# Schematic1_projectTSC_v31.net
KiCad netlist of a schematic drawn in EAGLE
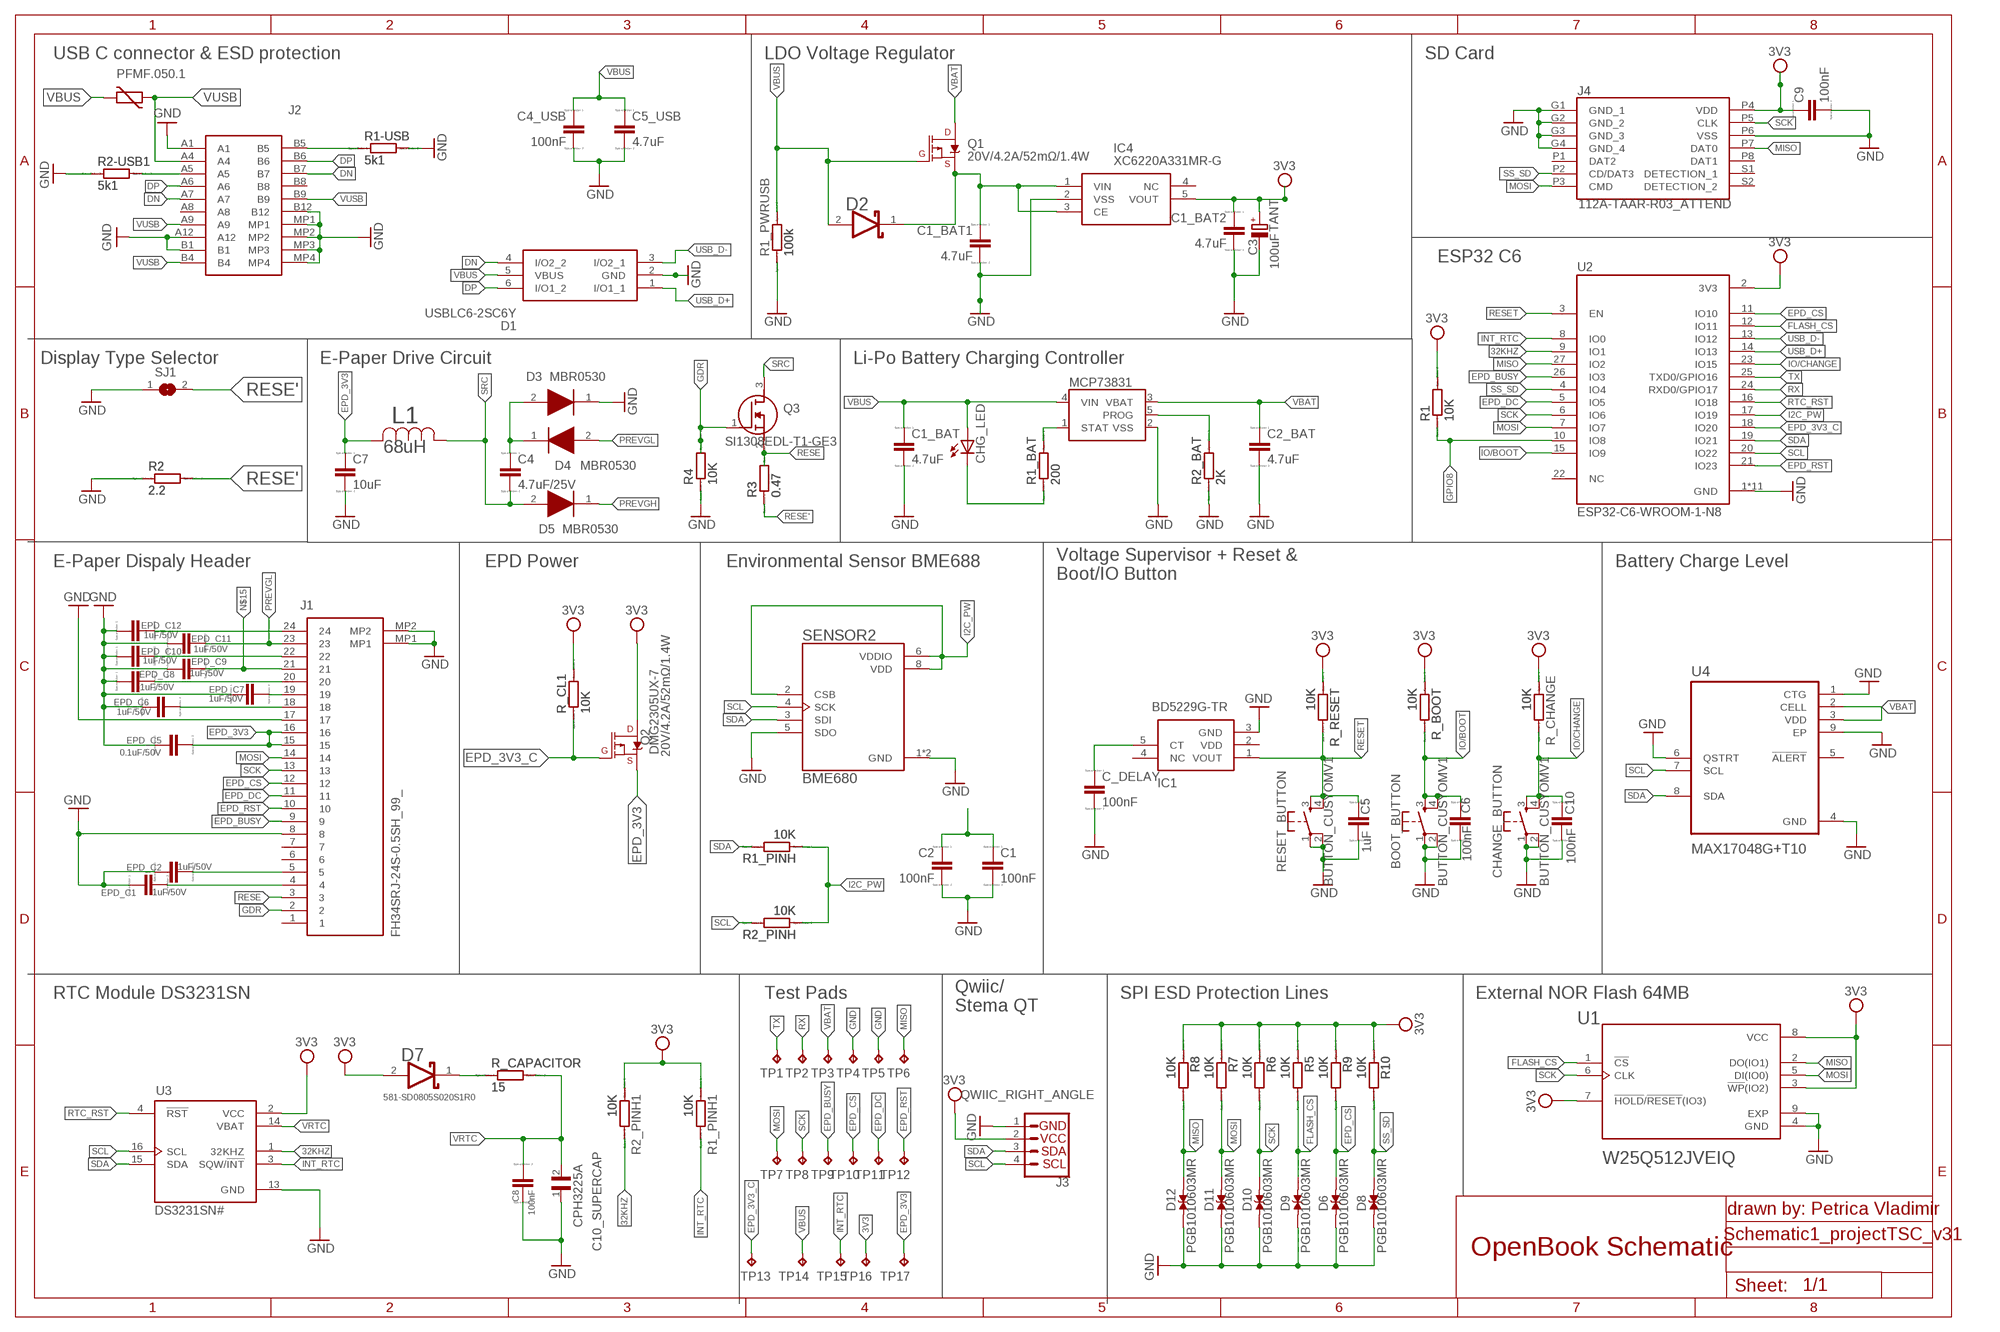
[diagram p0: schematic, sheet 1]

(export (version "E")
  (design (tool "Eeschema 10.0.6"))
  (components
    (comp (ref "BOOT_BUTTON")
      (value "BUTTON_CUSYOMV1")
      (footprint "eagle-import:MYBUTTON")
      (libsource (lib "eagle-import") (part "BUTTON_CUSYOMV1"))
    )
    (comp (ref "C1")
      (value "100nF")
      (footprint "eagle-import:EAGLE-LTSPICE_C0402")
      (libsource (lib "eagle-import") (part "EAGLE-LTSPICE_CC0402"))
    )
    (comp (ref "C1_BAT")
      (value "4.7uF")
      (footprint "eagle-import:EAGLE-LTSPICE_C0402")
      (libsource (lib "eagle-import") (part "EAGLE-LTSPICE_CC0402"))
    )
    (comp (ref "C1_BAT1")
      (value "4.7uF")
      (footprint "eagle-import:EAGLE-LTSPICE_C0402")
      (libsource (lib "eagle-import") (part "EAGLE-LTSPICE_CC0402"))
    )
    (comp (ref "C1_BAT2")
      (value "4.7uF")
      (footprint "eagle-import:EAGLE-LTSPICE_C0402")
      (libsource (lib "eagle-import") (part "EAGLE-LTSPICE_CC0402"))
    )
    (comp (ref "C2")
      (value "100nF")
      (footprint "eagle-import:EAGLE-LTSPICE_C0402")
      (libsource (lib "eagle-import") (part "EAGLE-LTSPICE_CC0402"))
    )
    (comp (ref "C2_BAT")
      (value "4.7uF")
      (footprint "eagle-import:EAGLE-LTSPICE_C0402")
      (libsource (lib "eagle-import") (part "EAGLE-LTSPICE_CC0402"))
    )
    (comp (ref "C3")
      (value "100uF")
      (footprint "eagle-import:RCL_CT3528")
      (libsource (lib "eagle-import") (part "RCL_CPOL-EUCT3528"))
    )
    (comp (ref "C4")
      (value "4.7uF/25V")
      (footprint "eagle-import:EAGLE-LTSPICE_C0402")
      (libsource (lib "eagle-import") (part "EAGLE-LTSPICE_CC0402"))
    )
    (comp (ref "C4_USB")
      (value "100nF")
      (footprint "eagle-import:EAGLE-LTSPICE_C0402")
      (libsource (lib "eagle-import") (part "EAGLE-LTSPICE_CC0402"))
    )
    (comp (ref "C5")
      (value "1uF")
      (footprint "eagle-import:EAGLE-LTSPICE_C0402")
      (libsource (lib "eagle-import") (part "EAGLE-LTSPICE_CC0402"))
    )
    (comp (ref "C5_USB")
      (value "4.7uF")
      (footprint "eagle-import:EAGLE-LTSPICE_C0402")
      (libsource (lib "eagle-import") (part "EAGLE-LTSPICE_CC0402"))
    )
    (comp (ref "C6")
      (value "100nF")
      (footprint "eagle-import:EAGLE-LTSPICE_C0402")
      (libsource (lib "eagle-import") (part "EAGLE-LTSPICE_CC0402"))
    )
    (comp (ref "C7")
      (value "10uF")
      (footprint "eagle-import:EAGLE-LTSPICE_C0402")
      (libsource (lib "eagle-import") (part "EAGLE-LTSPICE_CC0402"))
    )
    (comp (ref "C8")
      (value "100nF")
      (footprint "eagle-import:EAGLE-LTSPICE_C0402")
      (libsource (lib "eagle-import") (part "EAGLE-LTSPICE_CC0402"))
    )
    (comp (ref "C9")
      (value "100nF")
      (footprint "eagle-import:EAGLE-LTSPICE_C0402")
      (libsource (lib "eagle-import") (part "EAGLE-LTSPICE_CC0402"))
    )
    (comp (ref "C10")
      (value "100nF")
      (footprint "eagle-import:EAGLE-LTSPICE_C0402")
      (libsource (lib "eagle-import") (part "EAGLE-LTSPICE_CC0402"))
    )
    (comp (ref "C10_SUPERCAP")
      (value "CPH3225A")
      (footprint "eagle-import:CAPCP3225X100N")
      (fields (field (name "MF") "Seiko Instruments"))
      (libsource (lib "eagle-import") (part "CPH3225A"))
    )
    (comp (ref "CHANGE_BUTTON")
      (value "BUTTON_CUSYOMV1")
      (footprint "eagle-import:MYBUTTON")
      (libsource (lib "eagle-import") (part "BUTTON_CUSYOMV1"))
    )
    (comp (ref "CHG_LED")
      (value "ADAFRUIT_LEDCHIP-LED0603")
      (footprint "eagle-import:ADAFRUIT_CHIP-LED0603")
      (libsource (lib "eagle-import") (part "ADAFRUIT_LEDCHIP-LED0603"))
    )
    (comp (ref "C_DELAY")
      (value "100nF")
      (footprint "eagle-import:EAGLE-LTSPICE_C0402")
      (libsource (lib "eagle-import") (part "EAGLE-LTSPICE_CC0402"))
    )
    (comp (ref "D1")
      (value "USBLC6-2SC6Y")
      (footprint "eagle-import:SOT95P280X145-6N")
      (fields (field (name "MF") "STMicroelectronics"))
      (libsource (lib "eagle-import") (part "USBLC6-2SC6Y"))
    )
    (comp (ref "D2")
      (value "ESP32_WROVER_AVX---SD0805S020S1R0_AVX_SD0805S020S1R0_0_0AVX_SD0805S020S1R0_0_0")
      (footprint "eagle-import:ESP32_WROVER_AVX---SD0805S020S1R0_AVX_SD0805S020S1R0_0")
      (fields
        (field (name "DIGIKEY_PART_NUMBER") "478-7800-1-ND")
        (field (name "MF") "AVX")
        (field (name "MOUSER_PART_NUMBER") "581-SD0805S020S1R0")
      )
      (libsource (lib "eagle-import") (part "ESP32_WROVER_AVX---SD0805S020S1R0_AVX_SD0805S020S1R0_0_0AVX_SD0805S020S1R0_0_0"))
    )
    (comp (ref "D3")
      (value "MBR0530")
      (footprint "eagle-import:SOD3716X135N")
      (fields (field (name "MF") "ON Semiconductor"))
      (libsource (lib "eagle-import") (part "MBR0530"))
    )
    (comp (ref "D4")
      (value "MBR0530")
      (footprint "eagle-import:SOD3716X135N")
      (fields (field (name "MF") "ON Semiconductor"))
      (libsource (lib "eagle-import") (part "MBR0530"))
    )
    (comp (ref "D5")
      (value "MBR0530")
      (footprint "eagle-import:SOD3716X135N")
      (fields (field (name "MF") "ON Semiconductor"))
      (libsource (lib "eagle-import") (part "MBR0530"))
    )
    (comp (ref "D6")
      (value "PGB1010603MR")
      (footprint "eagle-import:DIOC1608X36N")
      (fields (field (name "MF") "Littelfuse Inc."))
      (libsource (lib "eagle-import") (part "PGB1010603MR"))
    )
    (comp (ref "D7")
      (value "ESP32_WROVER_AVX---SD0805S020S1R0_AVX_SD0805S020S1R0_0_0AVX_SD0805S020S1R0_0_0")
      (footprint "eagle-import:ESP32_WROVER_AVX---SD0805S020S1R0_AVX_SD0805S020S1R0_0")
      (fields
        (field (name "DIGIKEY_PART_NUMBER") "478-7800-1-ND")
        (field (name "MF") "AVX")
        (field (name "MOUSER_PART_NUMBER") "581-SD0805S020S1R0")
      )
      (libsource (lib "eagle-import") (part "ESP32_WROVER_AVX---SD0805S020S1R0_AVX_SD0805S020S1R0_0_0AVX_SD0805S020S1R0_0_0"))
    )
    (comp (ref "D8")
      (value "PGB1010603MR")
      (footprint "eagle-import:DIOC1608X36N")
      (fields (field (name "MF") "Littelfuse Inc."))
      (libsource (lib "eagle-import") (part "PGB1010603MR"))
    )
    (comp (ref "D9")
      (value "PGB1010603MR")
      (footprint "eagle-import:DIOC1608X36N")
      (fields (field (name "MF") "Littelfuse Inc."))
      (libsource (lib "eagle-import") (part "PGB1010603MR"))
    )
    (comp (ref "D10")
      (value "PGB1010603MR")
      (footprint "eagle-import:DIOC1608X36N")
      (fields (field (name "MF") "Littelfuse Inc."))
      (libsource (lib "eagle-import") (part "PGB1010603MR"))
    )
    (comp (ref "D11")
      (value "PGB1010603MR")
      (footprint "eagle-import:DIOC1608X36N")
      (fields (field (name "MF") "Littelfuse Inc."))
      (libsource (lib "eagle-import") (part "PGB1010603MR"))
    )
    (comp (ref "D12")
      (value "PGB1010603MR")
      (footprint "eagle-import:DIOC1608X36N")
      (fields (field (name "MF") "Littelfuse Inc."))
      (libsource (lib "eagle-import") (part "PGB1010603MR"))
    )
    (comp (ref "EPD_C1")
      (value "1uF/50V")
      (footprint "eagle-import:EAGLE-LTSPICE_C0402")
      (libsource (lib "eagle-import") (part "EAGLE-LTSPICE_CC0402"))
    )
    (comp (ref "EPD_C2")
      (value "1uF/50V")
      (footprint "eagle-import:EAGLE-LTSPICE_C0402")
      (libsource (lib "eagle-import") (part "EAGLE-LTSPICE_CC0402"))
    )
    (comp (ref "EPD_C5")
      (value "0.1uF/50V")
      (footprint "eagle-import:EAGLE-LTSPICE_C0402")
      (libsource (lib "eagle-import") (part "EAGLE-LTSPICE_CC0402"))
    )
    (comp (ref "EPD_C6")
      (value "1uF/50V")
      (footprint "eagle-import:EAGLE-LTSPICE_C0402")
      (libsource (lib "eagle-import") (part "EAGLE-LTSPICE_CC0402"))
    )
    (comp (ref "EPD_C7")
      (value "1uF/50V")
      (footprint "eagle-import:EAGLE-LTSPICE_C0402")
      (libsource (lib "eagle-import") (part "EAGLE-LTSPICE_CC0402"))
    )
    (comp (ref "EPD_C8")
      (value "1uF/50V")
      (footprint "eagle-import:EAGLE-LTSPICE_C0402")
      (libsource (lib "eagle-import") (part "EAGLE-LTSPICE_CC0402"))
    )
    (comp (ref "EPD_C9")
      (value "1uF/50V")
      (footprint "eagle-import:EAGLE-LTSPICE_C0402")
      (libsource (lib "eagle-import") (part "EAGLE-LTSPICE_CC0402"))
    )
    (comp (ref "EPD_C10")
      (value "1uF/50V")
      (footprint "eagle-import:EAGLE-LTSPICE_C0402")
      (libsource (lib "eagle-import") (part "EAGLE-LTSPICE_CC0402"))
    )
    (comp (ref "EPD_C11")
      (value "1uF/50V")
      (footprint "eagle-import:EAGLE-LTSPICE_C0402")
      (libsource (lib "eagle-import") (part "EAGLE-LTSPICE_CC0402"))
    )
    (comp (ref "EPD_C12")
      (value "1uF/50V")
      (footprint "eagle-import:EAGLE-LTSPICE_C0402")
      (libsource (lib "eagle-import") (part "EAGLE-LTSPICE_CC0402"))
    )
    (comp (ref "IC1")
      (value "BD5229G-TR")
      (footprint "eagle-import:SOT95P280X125-5N")
      (fields (field (name "MOUSER_PART_NUMBER") "755-BD5229G-TR"))
      (libsource (lib "eagle-import") (part "BD5229G-TR"))
    )
    (comp (ref "IC4")
      (value "XC6220A331MR-G")
      (footprint "eagle-import:SOT95P280X120-5N")
      (fields (field (name "MOUSER_PART_NUMBER") "865-XC6220A331MR-G"))
      (libsource (lib "eagle-import") (part "XC6220A331MR-G"))
    )
    (comp (ref "J1")
      (value "FH34SRJ-24S-0.5SH_99_")
      (footprint "eagle-import:FH34SRJ24S05SH99")
      (fields
        (field (name "MANUFACTURER_PART_NUMBER") "FH34SRJ-24S-0.5SH(99)")
        (field (name "MOUSER_PART_NUMBER") "798-FH34SRJ24S05SH99")
      )
      (libsource (lib "eagle-import") (part "FH34SRJ-24S-0.5SH_99_"))
    )
    (comp (ref "J2")
      (value "SAMACSYS_PARTS_USB4110-GF-A")
      (footprint "eagle-import:SAMACSYS_PARTS_USB4110GFA")
      (fields
        (field (name "MANUFACTURER_PART_NUMBER") "USB4110-GF-A")
        (field (name "MOUSER_PART_NUMBER") "640-USB4110-GF-A")
      )
      (libsource (lib "eagle-import") (part "SAMACSYS_PARTS_USB4110-GF-A"))
    )
    (comp (ref "J3")
      (value "QWIIC_RIGHT_ANGLE")
      (footprint "eagle-import:JST04_1MM_RA")
      (libsource (lib "eagle-import") (part "QWIIC_CONNECTORJS-1MM"))
    )
    (comp (ref "J4")
      (value "112A-TAAR-R03_ATTEND")
      (footprint "eagle-import:112ATAARR03ATTEND")
      (fields (field (name "MANUFACTURER_PART_NUMBER") "112A-TAAR-R03 ATTEND"))
      (libsource (lib "eagle-import") (part "112A-TAAR-R03_ATTEND"))
    )
    (comp (ref "L1")
      (value "744043680IND_4828-WE-TPC_WRE")
      (footprint "eagle-import:IND_4828-WE-TPC_WRE")
      (fields
        (field (name "MANUFACTURER_PART_NUMBER") "744043680")
        (field (name "MANUFACTURER_PART_NUMBER_1") "68uH")
        (field (name "COPYRIGHT") "Copyright (C) 2024 Ultra Librarian. All rights reserved.")
      )
      (libsource (lib "eagle-import") (part "744043680IND_4828-WE-TPC_WRE"))
    )
    (comp (ref "MCP73831")
      (value "ESP32_WROVER_SPARKFUN-IC-POWER_MCP73831")
      (footprint "eagle-import:ESP32_WROVER_SPARKFUN-IC-POWER_SOT23-5")
      (libsource (lib "eagle-import") (part "ESP32_WROVER_SPARKFUN-IC-POWER_MCP73831"))
    )
    (comp (ref "PFMF.050.1")
      (value "ESP32C6_VARISTORCN1812")
      (footprint "eagle-import:ESP32C6_VARISTOR_CT_CN1812")
      (libsource (lib "eagle-import") (part "ESP32C6_VARISTORCN1812"))
    )
    (comp (ref "Q1")
      (value "20V/4.2A/52mΩ/1.4W")
      (footprint "eagle-import:ESP32_WROVER_SPARKFUN-DISCRETESEMI_SOT23-3")
      (libsource (lib "eagle-import") (part "ESP32_WROVER_SPARKFUN-DISCRETESEMI_MOSFET_PCH-DMG2305UX-7"))
    )
    (comp (ref "Q2")
      (value "20V/4.2A/52mΩ/1.4W")
      (footprint "eagle-import:ESP32_WROVER_SPARKFUN-DISCRETESEMI_SOT23-3")
      (fields (field (name "PRODUCT") "DMG2305UX-7"))
      (libsource (lib "eagle-import") (part "ESP32_WROVER_SPARKFUN-DISCRETESEMI_MOSFET_PCH-DMG2305UX-7"))
    )
    (comp (ref "Q3")
      (value "SI1308EDL-T1-GE3")
      (footprint "eagle-import:SOT65P210X110-3N")
      (fields (field (name "MF") "Vishay Siliconix"))
      (libsource (lib "eagle-import") (part "SI1308EDL-T1-GE3"))
    )
    (comp (ref "R1")
      (value "10K")
      (footprint "eagle-import:ESP32_WROVER_EAGLE-LTSPICE_R0402")
      (libsource (lib "eagle-import") (part "ESP32_WROVER_EAGLE-LTSPICE_RR0402"))
    )
    (comp (ref "R1-USB")
      (value "5k1")
      (footprint "eagle-import:ESP32_WROVER_EAGLE-LTSPICE_R0402")
      (libsource (lib "eagle-import") (part "ESP32_WROVER_EAGLE-LTSPICE_RR0402"))
    )
    (comp (ref "R1_BAT")
      (value "200")
      (footprint "eagle-import:ESP32_WROVER_EAGLE-LTSPICE_R0402")
      (libsource (lib "eagle-import") (part "ESP32_WROVER_EAGLE-LTSPICE_RR0402"))
    )
    (comp (ref "R1_PINH")
      (value "10K")
      (footprint "eagle-import:ESP32_WROVER_EAGLE-LTSPICE_R0402")
      (libsource (lib "eagle-import") (part "ESP32_WROVER_EAGLE-LTSPICE_RR0402"))
    )
    (comp (ref "R1_PINH1")
      (value "10K")
      (footprint "eagle-import:ESP32_WROVER_EAGLE-LTSPICE_R0402")
      (libsource (lib "eagle-import") (part "ESP32_WROVER_EAGLE-LTSPICE_RR0402"))
    )
    (comp (ref "R1_PWRUSB")
      (value "100k")
      (footprint "eagle-import:ESP32_WROVER_EAGLE-LTSPICE_R0402")
      (libsource (lib "eagle-import") (part "ESP32_WROVER_EAGLE-LTSPICE_RR0402"))
    )
    (comp (ref "R2")
      (value "2.2")
      (footprint "eagle-import:ESP32_WROVER_EAGLE-LTSPICE_R0402")
      (libsource (lib "eagle-import") (part "ESP32_WROVER_EAGLE-LTSPICE_RR0402"))
    )
    (comp (ref "R2-USB1")
      (value "5k1")
      (footprint "eagle-import:ESP32_WROVER_EAGLE-LTSPICE_R0402")
      (libsource (lib "eagle-import") (part "ESP32_WROVER_EAGLE-LTSPICE_RR0402"))
    )
    (comp (ref "R2_BAT")
      (value "2K")
      (footprint "eagle-import:ESP32_WROVER_EAGLE-LTSPICE_R0402")
      (libsource (lib "eagle-import") (part "ESP32_WROVER_EAGLE-LTSPICE_RR0402"))
    )
    (comp (ref "R2_PINH")
      (value "10K")
      (footprint "eagle-import:ESP32_WROVER_EAGLE-LTSPICE_R0402")
      (libsource (lib "eagle-import") (part "ESP32_WROVER_EAGLE-LTSPICE_RR0402"))
    )
    (comp (ref "R2_PINH1")
      (value "10K")
      (footprint "eagle-import:ESP32_WROVER_EAGLE-LTSPICE_R0402")
      (libsource (lib "eagle-import") (part "ESP32_WROVER_EAGLE-LTSPICE_RR0402"))
    )
    (comp (ref "R3")
      (value "0.47")
      (footprint "eagle-import:ESP32_WROVER_EAGLE-LTSPICE_R0402")
      (libsource (lib "eagle-import") (part "ESP32_WROVER_EAGLE-LTSPICE_RR0402"))
    )
    (comp (ref "R4")
      (value "10K")
      (footprint "eagle-import:ESP32_WROVER_EAGLE-LTSPICE_R0402")
      (libsource (lib "eagle-import") (part "ESP32_WROVER_EAGLE-LTSPICE_RR0402"))
    )
    (comp (ref "R5")
      (value "10K")
      (footprint "eagle-import:ESP32_WROVER_EAGLE-LTSPICE_R0402")
      (libsource (lib "eagle-import") (part "ESP32_WROVER_EAGLE-LTSPICE_RR0402"))
    )
    (comp (ref "R6")
      (value "10K")
      (footprint "eagle-import:ESP32_WROVER_EAGLE-LTSPICE_R0402")
      (libsource (lib "eagle-import") (part "ESP32_WROVER_EAGLE-LTSPICE_RR0402"))
    )
    (comp (ref "R7")
      (value "10K")
      (footprint "eagle-import:ESP32_WROVER_EAGLE-LTSPICE_R0402")
      (libsource (lib "eagle-import") (part "ESP32_WROVER_EAGLE-LTSPICE_RR0402"))
    )
    (comp (ref "R8")
      (value "10K")
      (footprint "eagle-import:ESP32_WROVER_EAGLE-LTSPICE_R0402")
      (libsource (lib "eagle-import") (part "ESP32_WROVER_EAGLE-LTSPICE_RR0402"))
    )
    (comp (ref "R9")
      (value "10K")
      (footprint "eagle-import:ESP32_WROVER_EAGLE-LTSPICE_R0402")
      (libsource (lib "eagle-import") (part "ESP32_WROVER_EAGLE-LTSPICE_RR0402"))
    )
    (comp (ref "R10")
      (value "10K")
      (footprint "eagle-import:ESP32_WROVER_EAGLE-LTSPICE_R0402")
      (libsource (lib "eagle-import") (part "ESP32_WROVER_EAGLE-LTSPICE_RR0402"))
    )
    (comp (ref "RESET_BUTTON")
      (value "BUTTON_CUSYOMV1")
      (footprint "eagle-import:MYBUTTON")
      (libsource (lib "eagle-import") (part "BUTTON_CUSYOMV1"))
    )
    (comp (ref "R_BOOT")
      (value "10K")
      (footprint "eagle-import:ESP32_WROVER_EAGLE-LTSPICE_R0402")
      (libsource (lib "eagle-import") (part "ESP32_WROVER_EAGLE-LTSPICE_RR0402"))
    )
    (comp (ref "R_CAPACITOR")
      (value "15")
      (footprint "eagle-import:ESP32_WROVER_EAGLE-LTSPICE_R0402")
      (libsource (lib "eagle-import") (part "ESP32_WROVER_EAGLE-LTSPICE_RR0402"))
    )
    (comp (ref "R_CHANGE")
      (value "10K")
      (footprint "eagle-import:ESP32_WROVER_EAGLE-LTSPICE_R0402")
      (libsource (lib "eagle-import") (part "ESP32_WROVER_EAGLE-LTSPICE_RR0402"))
    )
    (comp (ref "R_CL1")
      (value "10K")
      (footprint "eagle-import:ESP32_WROVER_EAGLE-LTSPICE_R0402")
      (libsource (lib "eagle-import") (part "ESP32_WROVER_EAGLE-LTSPICE_RR0402"))
    )
    (comp (ref "R_RESET")
      (value "10K")
      (footprint "eagle-import:ESP32_WROVER_EAGLE-LTSPICE_R0402")
      (libsource (lib "eagle-import") (part "ESP32_WROVER_EAGLE-LTSPICE_RR0402"))
    )
    (comp (ref "SENSOR2")
      (value "ESP32_WROVER_BME680_BME680")
      (footprint "eagle-import:ESP32_WROVER_BME680_PSON80P300X300X100-8N")
      (fields (field (name "MF") "Bosch Sensortec") (field (name "MP") "BME680"))
      (libsource (lib "eagle-import") (part "ESP32_WROVER_BME680_BME680"))
    )
    (comp (ref "SJ1") (value "SJ") (footprint "eagle-import:SJ") (libsource (lib "eagle-import") (part "SJ")))
    (comp (ref "TP1")
      (value "TPTP20R")
      (footprint "eagle-import:TP20R")
      (libsource (lib "eagle-import") (part "TPTP20R"))
    )
    (comp (ref "TP2")
      (value "TPTP20R")
      (footprint "eagle-import:TP20R")
      (libsource (lib "eagle-import") (part "TPTP20R"))
    )
    (comp (ref "TP3")
      (value "TPTP20R")
      (footprint "eagle-import:TP20R")
      (libsource (lib "eagle-import") (part "TPTP20R"))
    )
    (comp (ref "TP4")
      (value "TPTP20R")
      (footprint "eagle-import:TP20R")
      (libsource (lib "eagle-import") (part "TPTP20R"))
    )
    (comp (ref "TP5")
      (value "TPTP20R")
      (footprint "eagle-import:TP20R")
      (libsource (lib "eagle-import") (part "TPTP20R"))
    )
    (comp (ref "TP6")
      (value "TPTP20R")
      (footprint "eagle-import:TP20R")
      (libsource (lib "eagle-import") (part "TPTP20R"))
    )
    (comp (ref "TP7")
      (value "TPTP20R")
      (footprint "eagle-import:TP20R")
      (libsource (lib "eagle-import") (part "TPTP20R"))
    )
    (comp (ref "TP8")
      (value "TPTP20R")
      (footprint "eagle-import:TP20R")
      (libsource (lib "eagle-import") (part "TPTP20R"))
    )
    (comp (ref "TP9")
      (value "TPTP20R")
      (footprint "eagle-import:TP20R")
      (libsource (lib "eagle-import") (part "TPTP20R"))
    )
    (comp (ref "TP10")
      (value "TPTP20R")
      (footprint "eagle-import:TP20R")
      (libsource (lib "eagle-import") (part "TPTP20R"))
    )
    (comp (ref "TP11")
      (value "TPTP20R")
      (footprint "eagle-import:TP20R")
      (libsource (lib "eagle-import") (part "TPTP20R"))
    )
    (comp (ref "TP12")
      (value "TPTP20R")
      (footprint "eagle-import:TP20R")
      (libsource (lib "eagle-import") (part "TPTP20R"))
    )
    (comp (ref "TP13")
      (value "TPTP20R")
      (footprint "eagle-import:TP20R")
      (libsource (lib "eagle-import") (part "TPTP20R"))
    )
    (comp (ref "TP14")
      (value "TPTP20R")
      (footprint "eagle-import:TP20R")
      (libsource (lib "eagle-import") (part "TPTP20R"))
    )
    (comp (ref "TP15")
      (value "TPTP20R")
      (footprint "eagle-import:TP20R")
      (libsource (lib "eagle-import") (part "TPTP20R"))
    )
    (comp (ref "TP16")
      (value "TPTP20R")
      (footprint "eagle-import:TP20R")
      (libsource (lib "eagle-import") (part "TPTP20R"))
    )
    (comp (ref "TP17")
      (value "TPTP20R")
      (footprint "eagle-import:TP20R")
      (libsource (lib "eagle-import") (part "TPTP20R"))
    )
    (comp (ref "U1")
      (value "W25Q512JVEIQ")
      (footprint "eagle-import:SON127P600X800X80-9N")
      (fields (field (name "MF") "Winbond Electronics"))
      (libsource (lib "eagle-import") (part "W25Q512JVEIQ"))
    )
    (comp (ref "U2")
      (value "ESP32-C6-WROOM-1-N8")
      (footprint "eagle-import:XCVR_ESP32-C6-WROOM-1-N8")
      (fields (field (name "MF") "Espressif Systems"))
      (libsource (lib "eagle-import") (part "ESP32-C6-WROOM-1-N8"))
    )
    (comp (ref "U3")
      (value "DS3231SN#")
      (footprint "eagle-import:SOIC127P1032X265-16N")
      (fields (field (name "MF") "Analog Devices"))
      (libsource (lib "eagle-import") (part "DS3231SN#"))
    )
    (comp (ref "U4")
      (value "MAX17048G+T10")
      (footprint "eagle-import:SON50P200X200X80-9N")
      (fields (field (name "MF") "Analog Devices"))
      (libsource (lib "eagle-import") (part "MAX17048G+T10"))
    )
  )
  (nets
    (net (code "1") (name "3V3") (class "Default")
      (node (ref "C1_BAT2") (pin "1") (pinfunction "1_1") (pintype "passive"))
      (node (ref "C3") (pin "+") (pinfunction "+_+") (pintype "passive"))
      (node (ref "C9") (pin "1") (pinfunction "1_1") (pintype "passive"))
      (node (ref "D7") (pin "2") (pinfunction "ANODE_2") (pintype "bidirectional"))
      (node (ref "IC4") (pin "5") (pinfunction "VOUT_5") (pintype "bidirectional"))
      (node (ref "J3") (pin "2") (pinfunction "2_2") (pintype "power_in"))
      (node (ref "J4") (pin "P4") (pinfunction "VDD_P4") (pintype "bidirectional"))
      (node (ref "Q2") (pin "3") (pinfunction "D_3") (pintype "bidirectional"))
      (node (ref "R1") (pin "2") (pinfunction "2_2") (pintype "passive"))
      (node (ref "R10") (pin "1") (pinfunction "1_1") (pintype "passive"))
      (node (ref "R1_PINH1") (pin "1") (pinfunction "1_1") (pintype "passive"))
      (node (ref "R2_PINH1") (pin "1") (pinfunction "1_1") (pintype "passive"))
      (node (ref "R5") (pin "1") (pinfunction "1_1") (pintype "passive"))
      (node (ref "R6") (pin "1") (pinfunction "1_1") (pintype "passive"))
      (node (ref "R7") (pin "1") (pinfunction "1_1") (pintype "passive"))
      (node (ref "R8") (pin "1") (pinfunction "1_1") (pintype "passive"))
      (node (ref "R9") (pin "1") (pinfunction "1_1") (pintype "passive"))
      (node (ref "R_BOOT") (pin "1") (pinfunction "1_1") (pintype "passive"))
      (node (ref "R_CHANGE") (pin "1") (pinfunction "1_1") (pintype "passive"))
      (node (ref "R_CL1") (pin "2") (pinfunction "2_2") (pintype "passive"))
      (node (ref "R_RESET") (pin "1") (pinfunction "1_1") (pintype "passive"))
      (node (ref "TP16") (pin "TP") (pinfunction "TP_TP") (pintype "input"))
      (node (ref "U1") (pin "3") (pinfunction "~{WP}(IO2)_3") (pintype "bidirectional"))
      (node (ref "U1") (pin "7") (pinfunction "~{HOLD}/~{RESET}(IO3)_7") (pintype "bidirectional"))
      (node (ref "U1") (pin "8") (pinfunction "VCC_8") (pintype "power_in"))
      (node (ref "U2") (pin "2") (pinfunction "3V3_2") (pintype "power_in"))
      (node (ref "U3") (pin "2") (pinfunction "VCC_2") (pintype "power_in"))
    )
    (net (code "2") (name "32KHZ") (class "Default")
      (node (ref "R2_PINH1") (pin "2") (pinfunction "2_2") (pintype "passive"))
      (node (ref "U2") (pin "9") (pinfunction "IO1_9") (pintype "bidirectional"))
      (node (ref "U3") (pin "1") (pinfunction "32KHZ_1") (pintype "output"))
    )
    (net (code "3") (name "DN") (class "Default")
      (node (ref "D1") (pin "4") (pinfunction "I/O2_2_4") (pintype "bidirectional"))
      (node (ref "J2") (pin "A7") (pinfunction "A7_A7") (pintype "bidirectional"))
      (node (ref "J2") (pin "B7") (pinfunction "B7_B7") (pintype "bidirectional"))
    )
    (net (code "4") (name "DP") (class "Default")
      (node (ref "D1") (pin "6") (pinfunction "I/O1_2_6") (pintype "bidirectional"))
      (node (ref "J2") (pin "A6") (pinfunction "A6_A6") (pintype "bidirectional"))
      (node (ref "J2") (pin "B6") (pinfunction "B6_B6") (pintype "bidirectional"))
    )
    (net (code "5") (name "EPD_3V3") (class "Default")
      (node (ref "C7") (pin "1") (pinfunction "1_1") (pintype "passive"))
      (node (ref "EPD_C5") (pin "2") (pinfunction "2_2") (pintype "passive"))
      (node (ref "J1") (pin "15") (pinfunction "15_15") (pintype "bidirectional"))
      (node (ref "J1") (pin "16") (pinfunction "16_16") (pintype "bidirectional"))
      (node (ref "L1") (pin "2") (pinfunction "2_2") (pintype "passive"))
      (node (ref "Q2") (pin "2") (pinfunction "S_2") (pintype "bidirectional"))
      (node (ref "TP17") (pin "TP") (pinfunction "TP_TP") (pintype "input"))
    )
    (net (code "6") (name "EPD_3V3_C") (class "Default")
      (node (ref "Q2") (pin "1") (pinfunction "G_1") (pintype "bidirectional"))
      (node (ref "R_CL1") (pin "1") (pinfunction "1_1") (pintype "passive"))
      (node (ref "TP13") (pin "TP") (pinfunction "TP_TP") (pintype "input"))
      (node (ref "U2") (pin "18") (pinfunction "IO20_18") (pintype "bidirectional"))
    )
    (net (code "7") (name "EPD_BUSY") (class "Default")
      (node (ref "J1") (pin "9") (pinfunction "9_9") (pintype "bidirectional"))
      (node (ref "TP9") (pin "TP") (pinfunction "TP_TP") (pintype "input"))
      (node (ref "U2") (pin "26") (pinfunction "IO3_26") (pintype "bidirectional"))
    )
    (net (code "8") (name "EPD_CS") (class "Default")
      (node (ref "D6") (pin "2") (pinfunction "2_2") (pintype "passive"))
      (node (ref "J1") (pin "12") (pinfunction "12_12") (pintype "bidirectional"))
      (node (ref "R9") (pin "2") (pinfunction "2_2") (pintype "passive"))
      (node (ref "TP10") (pin "TP") (pinfunction "TP_TP") (pintype "input"))
      (node (ref "U2") (pin "11") (pinfunction "IO10_11") (pintype "bidirectional"))
    )
    (net (code "9") (name "EPD_DC") (class "Default")
      (node (ref "J1") (pin "11") (pinfunction "11_11") (pintype "bidirectional"))
      (node (ref "TP11") (pin "TP") (pinfunction "TP_TP") (pintype "input"))
      (node (ref "U2") (pin "5") (pinfunction "IO5_5") (pintype "bidirectional"))
    )
    (net (code "10") (name "EPD_RST") (class "Default")
      (node (ref "J1") (pin "10") (pinfunction "10_10") (pintype "bidirectional"))
      (node (ref "TP12") (pin "TP") (pinfunction "TP_TP") (pintype "input"))
      (node (ref "U2") (pin "21") (pinfunction "IO23_21") (pintype "bidirectional"))
    )
    (net (code "11") (name "FLASH_CS") (class "Default")
      (node (ref "D9") (pin "2") (pinfunction "2_2") (pintype "passive"))
      (node (ref "R5") (pin "2") (pinfunction "2_2") (pintype "passive"))
      (node (ref "U1") (pin "1") (pinfunction "~{CS}_1") (pintype "input"))
      (node (ref "U2") (pin "12") (pinfunction "IO11_12") (pintype "bidirectional"))
    )
    (net (code "12") (name "GDR") (class "Default")
      (node (ref "J1") (pin "2") (pinfunction "2_2") (pintype "bidirectional"))
      (node (ref "Q3") (pin "1") (pinfunction "G_1") (pintype "bidirectional"))
      (node (ref "R4") (pin "2") (pinfunction "2_2") (pintype "passive"))
    )
    (net (code "13") (name "GND") (class "Default")
      (node (ref "BOOT_BUTTON") (pin "1") (pinfunction "1_1") (pintype "passive"))
      (node (ref "BOOT_BUTTON") (pin "2") (pinfunction "2_2") (pintype "passive"))
      (node (ref "C1") (pin "2") (pinfunction "2_2") (pintype "passive"))
      (node (ref "C10") (pin "2") (pinfunction "2_2") (pintype "passive"))
      (node (ref "C10_SUPERCAP") (pin "1") (pinfunction "1_1") (pintype "passive"))
      (node (ref "C1_BAT") (pin "2") (pinfunction "2_2") (pintype "passive"))
      (node (ref "C1_BAT1") (pin "2") (pinfunction "2_2") (pintype "passive"))
      (node (ref "C1_BAT2") (pin "2") (pinfunction "2_2") (pintype "passive"))
      (node (ref "C2") (pin "2") (pinfunction "2_2") (pintype "passive"))
      (node (ref "C2_BAT") (pin "2") (pinfunction "2_2") (pintype "passive"))
      (node (ref "C3") (pin "-") (pinfunction "-_-") (pintype "passive"))
      (node (ref "C4_USB") (pin "2") (pinfunction "2_2") (pintype "passive"))
      (node (ref "C5") (pin "2") (pinfunction "2_2") (pintype "passive"))
      (node (ref "C5_USB") (pin "2") (pinfunction "2_2") (pintype "passive"))
      (node (ref "C6") (pin "2") (pinfunction "2_2") (pintype "passive"))
      (node (ref "C7") (pin "2") (pinfunction "2_2") (pintype "passive"))
      (node (ref "C8") (pin "1") (pinfunction "1_1") (pintype "passive"))
      (node (ref "C9") (pin "2") (pinfunction "2_2") (pintype "passive"))
      (node (ref "CHANGE_BUTTON") (pin "1") (pinfunction "1_1") (pintype "passive"))
      (node (ref "CHANGE_BUTTON") (pin "2") (pinfunction "2_2") (pintype "passive"))
      (node (ref "C_DELAY") (pin "2") (pinfunction "2_2") (pintype "passive"))
      (node (ref "D1") (pin "2") (pinfunction "GND_2") (pintype "bidirectional"))
      (node (ref "D10") (pin "1") (pinfunction "1_1") (pintype "passive"))
      (node (ref "D11") (pin "1") (pinfunction "1_1") (pintype "passive"))
      (node (ref "D12") (pin "1") (pinfunction "1_1") (pintype "passive"))
      (node (ref "D3") (pin "1") (pinfunction "K_1") (pintype "bidirectional"))
      (node (ref "D6") (pin "1") (pinfunction "1_1") (pintype "passive"))
      (node (ref "D8") (pin "1") (pinfunction "1_1") (pintype "passive"))
      (node (ref "D9") (pin "1") (pinfunction "1_1") (pintype "passive"))
      (node (ref "EPD_C1") (pin "1") (pinfunction "1_1") (pintype "passive"))
      (node (ref "EPD_C10") (pin "1") (pinfunction "1_1") (pintype "passive"))
      (node (ref "EPD_C11") (pin "1") (pinfunction "1_1") (pintype "passive"))
      (node (ref "EPD_C12") (pin "1") (pinfunction "1_1") (pintype "passive"))
      (node (ref "EPD_C2") (pin "1") (pinfunction "1_1") (pintype "passive"))
      (node (ref "EPD_C5") (pin "1") (pinfunction "1_1") (pintype "passive"))
      (node (ref "EPD_C6") (pin "1") (pinfunction "1_1") (pintype "passive"))
      (node (ref "EPD_C7") (pin "1") (pinfunction "1_1") (pintype "passive"))
      (node (ref "EPD_C8") (pin "1") (pinfunction "1_1") (pintype "passive"))
      (node (ref "EPD_C9") (pin "1") (pinfunction "1_1") (pintype "passive"))
      (node (ref "IC1") (pin "3") (pinfunction "GND_3") (pintype "bidirectional"))
      (node (ref "IC4") (pin "2") (pinfunction "VSS_2") (pintype "bidirectional"))
      (node (ref "J1") (pin "17") (pinfunction "17_17") (pintype "bidirectional"))
      (node (ref "J1") (pin "8") (pinfunction "8_8") (pintype "bidirectional"))
      (node (ref "J1") (pin "MP1") (pinfunction "MP1_MP1") (pintype "bidirectional"))
      (node (ref "J1") (pin "MP2") (pinfunction "MP2_MP2") (pintype "bidirectional"))
      (node (ref "J2") (pin "A1") (pinfunction "A1_A1") (pintype "bidirectional"))
      (node (ref "J2") (pin "A12") (pinfunction "A12_A12") (pintype "bidirectional"))
      (node (ref "J2") (pin "B1") (pinfunction "B1_B1") (pintype "bidirectional"))
      (node (ref "J2") (pin "B12") (pinfunction "B12_B12") (pintype "bidirectional"))
      (node (ref "J2") (pin "MP1") (pinfunction "MP1_MP1") (pintype "bidirectional"))
      (node (ref "J2") (pin "MP2") (pinfunction "MP2_MP2") (pintype "bidirectional"))
      (node (ref "J2") (pin "MP3") (pinfunction "MP3_MP3") (pintype "bidirectional"))
      (node (ref "J2") (pin "MP4") (pinfunction "MP4_MP4") (pintype "bidirectional"))
      (node (ref "J3") (pin "1") (pinfunction "1_1") (pintype "power_in"))
      (node (ref "J4") (pin "G1") (pinfunction "GND_1_G1") (pintype "bidirectional"))
      (node (ref "J4") (pin "G2") (pinfunction "GND_2_G2") (pintype "bidirectional"))
      (node (ref "J4") (pin "G3") (pinfunction "GND_3_G3") (pintype "bidirectional"))
      (node (ref "J4") (pin "G4") (pinfunction "GND_4_G4") (pintype "bidirectional"))
      (node (ref "J4") (pin "P6") (pinfunction "VSS_P6") (pintype "bidirectional"))
      (node (ref "MCP73831") (pin "2") (pinfunction "VSS_2") (pintype "power_in"))
      (node (ref "R1-USB") (pin "2") (pinfunction "2_2") (pintype "passive"))
      (node (ref "R1_PWRUSB") (pin "1") (pinfunction "1_1") (pintype "passive"))
      (node (ref "R2") (pin "1") (pinfunction "1_1") (pintype "passive"))
      (node (ref "R2-USB1") (pin "1") (pinfunction "1_1") (pintype "passive"))
      (node (ref "R2_BAT") (pin "1") (pinfunction "1_1") (pintype "passive"))
      (node (ref "R4") (pin "1") (pinfunction "1_1") (pintype "passive"))
      (node (ref "RESET_BUTTON") (pin "1") (pinfunction "1_1") (pintype "passive"))
      (node (ref "RESET_BUTTON") (pin "2") (pinfunction "2_2") (pintype "passive"))
      (node (ref "SENSOR2") (pin "1") (pinfunction "GND_1") (pintype "power_in"))
      (node (ref "SENSOR2") (pin "5") (pinfunction "SDO_5") (pintype "bidirectional"))
      (node (ref "SENSOR2") (pin "7") (pinfunction "GND_7") (pintype "power_in"))
      (node (ref "SJ1") (pin "1") (pinfunction "1_1") (pintype "passive"))
      (node (ref "TP4") (pin "TP") (pinfunction "TP_TP") (pintype "input"))
      (node (ref "TP5") (pin "TP") (pinfunction "TP_TP") (pintype "input"))
      (node (ref "U1") (pin "4") (pinfunction "GND_4") (pintype "power_in"))
      (node (ref "U1") (pin "9") (pinfunction "EXP_9") (pintype "passive"))
      (node (ref "U2") (pin "1") (pinfunction "GND_1") (pintype "power_in"))
      (node (ref "U2") (pin "28") (pinfunction "GND_28") (pintype "power_in"))
      (node (ref "U2") (pin "29_1") (pinfunction "GND_29_1") (pintype "power_in"))
      (node (ref "U2") (pin "29_2") (pinfunction "GND_29_2") (pintype "power_in"))
      (node (ref "U2") (pin "29_3") (pinfunction "GND_29_3") (pintype "power_in"))
      (node (ref "U2") (pin "29_4") (pinfunction "GND_29_4") (pintype "power_in"))
      (node (ref "U2") (pin "29_5") (pinfunction "GND_29_5") (pintype "power_in"))
      (node (ref "U2") (pin "29_6") (pinfunction "GND_29_6") (pintype "power_in"))
      (node (ref "U2") (pin "29_7") (pinfunction "GND_29_7") (pintype "power_in"))
      (node (ref "U2") (pin "29_8") (pinfunction "GND_29_8") (pintype "power_in"))
      (node (ref "U2") (pin "29_9") (pinfunction "GND_29_9") (pintype "power_in"))
      (node (ref "U3") (pin "13") (pinfunction "GND_13") (pintype "power_in"))
      (node (ref "U4") (pin "1") (pinfunction "CTG_1") (pintype "power_in"))
      (node (ref "U4") (pin "4") (pinfunction "GND_4") (pintype "power_in"))
      (node (ref "U4") (pin "6") (pinfunction "QSTRT_6") (pintype "input"))
      (node (ref "U4") (pin "9") (pinfunction "EP_9") (pintype "power_in"))
    )
    (net (code "14") (name "GPIO8") (class "Default")
      (node (ref "R1") (pin "1") (pinfunction "1_1") (pintype "passive"))
      (node (ref "U2") (pin "10") (pinfunction "IO8_10") (pintype "bidirectional"))
    )
    (net (code "15") (name "I2C_PW") (class "Default")
      (node (ref "R1_PINH") (pin "1") (pinfunction "1_1") (pintype "passive"))
      (node (ref "R2_PINH") (pin "1") (pinfunction "1_1") (pintype "passive"))
      (node (ref "SENSOR2") (pin "2") (pinfunction "CSB_2") (pintype "input"))
      (node (ref "SENSOR2") (pin "6") (pinfunction "VDDIO_6") (pintype "power_in"))
      (node (ref "SENSOR2") (pin "8") (pinfunction "VDD_8") (pintype "power_in"))
      (node (ref "U2") (pin "17") (pinfunction "IO19_17") (pintype "bidirectional"))
    )
    (net (code "16") (name "INT_RTC") (class "Default")
      (node (ref "R1_PINH1") (pin "2") (pinfunction "2_2") (pintype "passive"))
      (node (ref "TP15") (pin "TP") (pinfunction "TP_TP") (pintype "input"))
      (node (ref "U2") (pin "8") (pinfunction "IO0_8") (pintype "bidirectional"))
      (node (ref "U3") (pin "3") (pinfunction "SQW/~{INT}_3") (pintype "output"))
    )
    (net (code "17") (name "IO{slash}BOOT") (class "Default")
      (node (ref "BOOT_BUTTON") (pin "3") (pinfunction "3_3") (pintype "passive"))
      (node (ref "BOOT_BUTTON") (pin "4") (pinfunction "4_4") (pintype "passive"))
      (node (ref "C6") (pin "1") (pinfunction "1_1") (pintype "passive"))
      (node (ref "R_BOOT") (pin "2") (pinfunction "2_2") (pintype "passive"))
      (node (ref "U2") (pin "15") (pinfunction "IO9_15") (pintype "bidirectional"))
    )
    (net (code "18") (name "IO{slash}CHANGE") (class "Default")
      (node (ref "C10") (pin "1") (pinfunction "1_1") (pintype "passive"))
      (node (ref "CHANGE_BUTTON") (pin "3") (pinfunction "3_3") (pintype "passive"))
      (node (ref "CHANGE_BUTTON") (pin "4") (pinfunction "4_4") (pintype "passive"))
      (node (ref "R_CHANGE") (pin "2") (pinfunction "2_2") (pintype "passive"))
      (node (ref "U2") (pin "23") (pinfunction "IO15_23") (pintype "bidirectional"))
    )
    (net (code "19") (name "MISO") (class "Default")
      (node (ref "D12") (pin "2") (pinfunction "2_2") (pintype "passive"))
      (node (ref "J4") (pin "P7") (pinfunction "DAT0_P7") (pintype "bidirectional"))
      (node (ref "R8") (pin "2") (pinfunction "2_2") (pintype "passive"))
      (node (ref "TP6") (pin "TP") (pinfunction "TP_TP") (pintype "input"))
      (node (ref "U1") (pin "2") (pinfunction "DO(IO1)_2") (pintype "bidirectional"))
      (node (ref "U2") (pin "27") (pinfunction "IO2_27") (pintype "bidirectional"))
    )
    (net (code "20") (name "MOSI") (class "Default")
      (node (ref "D11") (pin "2") (pinfunction "2_2") (pintype "passive"))
      (node (ref "J1") (pin "14") (pinfunction "14_14") (pintype "bidirectional"))
      (node (ref "J4") (pin "P3") (pinfunction "CMD_P3") (pintype "bidirectional"))
      (node (ref "R7") (pin "2") (pinfunction "2_2") (pintype "passive"))
      (node (ref "TP7") (pin "TP") (pinfunction "TP_TP") (pintype "input"))
      (node (ref "U1") (pin "5") (pinfunction "DI(IO0)_5") (pintype "bidirectional"))
      (node (ref "U2") (pin "7") (pinfunction "IO7_7") (pintype "bidirectional"))
    )
    (net (code "21") (name "N$15") (class "Default")
      (node (ref "EPD_C9") (pin "2") (pinfunction "2_2") (pintype "passive"))
      (node (ref "J1") (pin "21") (pinfunction "21_21") (pintype "bidirectional"))
    )
    (net (code "22") (name "Net-(C1-Pad1)") (class "Default")
      (node (ref "C1") (pin "1") (pinfunction "1_1") (pintype "passive"))
      (node (ref "C2") (pin "1") (pinfunction "1_1") (pintype "passive"))
    )
    (net (code "23") (name "Net-(CHG_LED-PadC)") (class "Default")
      (node (ref "CHG_LED") (pin "C") (pinfunction "C_C") (pintype "passive"))
      (node (ref "R1_BAT") (pin "1") (pinfunction "1_1") (pintype "passive"))
    )
    (net (code "24") (name "Net-(D2-CATHODE)") (class "Default")
      (node (ref "C1_BAT1") (pin "1") (pinfunction "1_1") (pintype "passive"))
      (node (ref "D2") (pin "1") (pinfunction "CATHODE_1") (pintype "bidirectional"))
      (node (ref "IC4") (pin "1") (pinfunction "VIN_1") (pintype "bidirectional"))
      (node (ref "IC4") (pin "3") (pinfunction "CE_3") (pintype "bidirectional"))
      (node (ref "Q1") (pin "2") (pinfunction "S_2") (pintype "bidirectional"))
    )
    (net (code "25") (name "Net-(D3-A)") (class "Default")
      (node (ref "C4") (pin "1") (pinfunction "1_1") (pintype "passive"))
      (node (ref "D3") (pin "2") (pinfunction "A_2") (pintype "bidirectional"))
      (node (ref "D4") (pin "1") (pinfunction "K_1") (pintype "bidirectional"))
    )
    (net (code "26") (name "Net-(D7-CATHODE)") (class "Default")
      (node (ref "D7") (pin "1") (pinfunction "CATHODE_1") (pintype "bidirectional"))
      (node (ref "R_CAPACITOR") (pin "1") (pinfunction "1_1") (pintype "passive"))
    )
    (net (code "27") (name "Net-(EPD_C1-Pad2)") (class "Default")
      (node (ref "EPD_C1") (pin "2") (pinfunction "2_2") (pintype "passive"))
      (node (ref "J1") (pin "4") (pinfunction "4_4") (pintype "bidirectional"))
    )
    (net (code "28") (name "Net-(EPD_C2-Pad2)") (class "Default")
      (node (ref "EPD_C2") (pin "2") (pinfunction "2_2") (pintype "passive"))
      (node (ref "J1") (pin "5") (pinfunction "5_5") (pintype "bidirectional"))
    )
    (net (code "29") (name "Net-(EPD_C6-Pad2)") (class "Default")
      (node (ref "EPD_C6") (pin "2") (pinfunction "2_2") (pintype "passive"))
      (node (ref "J1") (pin "18") (pinfunction "18_18") (pintype "bidirectional"))
    )
    (net (code "30") (name "Net-(EPD_C7-Pad2)") (class "Default")
      (node (ref "EPD_C7") (pin "2") (pinfunction "2_2") (pintype "passive"))
      (node (ref "J1") (pin "19") (pinfunction "19_19") (pintype "bidirectional"))
    )
    (net (code "31") (name "Net-(EPD_C8-Pad2)") (class "Default")
      (node (ref "EPD_C8") (pin "2") (pinfunction "2_2") (pintype "passive"))
      (node (ref "J1") (pin "20") (pinfunction "20_20") (pintype "bidirectional"))
    )
    (net (code "32") (name "Net-(EPD_C10-Pad2)") (class "Default")
      (node (ref "EPD_C10") (pin "2") (pinfunction "2_2") (pintype "passive"))
      (node (ref "J1") (pin "22") (pinfunction "22_22") (pintype "bidirectional"))
    )
    (net (code "33") (name "Net-(EPD_C12-Pad2)") (class "Default")
      (node (ref "EPD_C12") (pin "2") (pinfunction "2_2") (pintype "passive"))
      (node (ref "J1") (pin "24") (pinfunction "24_24") (pintype "bidirectional"))
    )
    (net (code "34") (name "Net-(IC1-CT)") (class "Default")
      (node (ref "C_DELAY") (pin "1") (pinfunction "1_1") (pintype "passive"))
      (node (ref "IC1") (pin "5") (pinfunction "CT_5") (pintype "bidirectional"))
    )
    (net (code "35") (name "Net-(J2-PadA5)") (class "Default")
      (node (ref "J2") (pin "A5") (pinfunction "A5_A5") (pintype "bidirectional"))
      (node (ref "R2-USB1") (pin "2") (pinfunction "2_2") (pintype "passive"))
    )
    (net (code "36") (name "Net-(J2-PadB5)") (class "Default")
      (node (ref "J2") (pin "B5") (pinfunction "B5_B5") (pintype "bidirectional"))
      (node (ref "R1-USB") (pin "1") (pinfunction "1_1") (pintype "passive"))
    )
    (net (code "37") (name "Net-(MCP73831-PROG)") (class "Default")
      (node (ref "MCP73831") (pin "5") (pinfunction "PROG_5") (pintype "input"))
      (node (ref "R2_BAT") (pin "2") (pinfunction "2_2") (pintype "passive"))
    )
    (net (code "38") (name "Net-(MCP73831-STAT)") (class "Default")
      (node (ref "MCP73831") (pin "1") (pinfunction "STAT_1") (pintype "output"))
      (node (ref "R1_BAT") (pin "2") (pinfunction "2_2") (pintype "passive"))
    )
    (net (code "39") (name "PREVGH") (class "Default")
      (node (ref "D5") (pin "1") (pinfunction "K_1") (pintype "bidirectional"))
    )
    (net (code "40") (name "PREVGL") (class "Default")
      (node (ref "D4") (pin "2") (pinfunction "A_2") (pintype "bidirectional"))
      (node (ref "EPD_C11") (pin "2") (pinfunction "2_2") (pintype "passive"))
      (node (ref "J1") (pin "23") (pinfunction "23_23") (pintype "bidirectional"))
    )
    (net (code "41") (name "RESE") (class "Default")
      (node (ref "J1") (pin "3") (pinfunction "3_3") (pintype "bidirectional"))
      (node (ref "Q3") (pin "2") (pinfunction "S_2") (pintype "bidirectional"))
      (node (ref "R3") (pin "2") (pinfunction "2_2") (pintype "passive"))
    )
    (net (code "42") (name "RESE'") (class "Default")
      (node (ref "R2") (pin "2") (pinfunction "2_2") (pintype "passive"))
      (node (ref "R3") (pin "1") (pinfunction "1_1") (pintype "passive"))
      (node (ref "SJ1") (pin "2") (pinfunction "2_2") (pintype "passive"))
    )
    (net (code "43") (name "RESET") (class "Default")
      (node (ref "C5") (pin "1") (pinfunction "1_1") (pintype "passive"))
      (node (ref "IC1") (pin "1") (pinfunction "VOUT_1") (pintype "bidirectional"))
      (node (ref "RESET_BUTTON") (pin "3") (pinfunction "3_3") (pintype "passive"))
      (node (ref "RESET_BUTTON") (pin "4") (pinfunction "4_4") (pintype "passive"))
      (node (ref "R_RESET") (pin "2") (pinfunction "2_2") (pintype "passive"))
      (node (ref "U2") (pin "3") (pinfunction "EN_3") (pintype "input"))
    )
    (net (code "44") (name "RTC_RST") (class "Default")
      (node (ref "U2") (pin "16") (pinfunction "IO18_16") (pintype "bidirectional"))
      (node (ref "U3") (pin "4") (pinfunction "~{RST}_4") (pintype "input"))
    )
    (net (code "45") (name "RX") (class "Default")
      (node (ref "TP2") (pin "TP") (pinfunction "TP_TP") (pintype "input"))
      (node (ref "U2") (pin "24") (pinfunction "RXD0/GPIO17_24") (pintype "bidirectional"))
    )
    (net (code "46") (name "SCK") (class "Default")
      (node (ref "D10") (pin "2") (pinfunction "2_2") (pintype "passive"))
      (node (ref "J1") (pin "13") (pinfunction "13_13") (pintype "bidirectional"))
      (node (ref "J4") (pin "P5") (pinfunction "CLK_P5") (pintype "bidirectional"))
      (node (ref "R6") (pin "2") (pinfunction "2_2") (pintype "passive"))
      (node (ref "TP8") (pin "TP") (pinfunction "TP_TP") (pintype "input"))
      (node (ref "U1") (pin "6") (pinfunction "CLK_6") (pintype "input"))
      (node (ref "U2") (pin "6") (pinfunction "IO6_6") (pintype "bidirectional"))
    )
    (net (code "47") (name "SCL") (class "Default")
      (node (ref "J3") (pin "4") (pinfunction "4_4") (pintype "passive"))
      (node (ref "R2_PINH") (pin "2") (pinfunction "2_2") (pintype "passive"))
      (node (ref "SENSOR2") (pin "4") (pinfunction "SCK_4") (pintype "input"))
      (node (ref "U2") (pin "20") (pinfunction "IO22_20") (pintype "bidirectional"))
      (node (ref "U3") (pin "16") (pinfunction "SCL_16") (pintype "input"))
      (node (ref "U4") (pin "7") (pinfunction "SCL_7") (pintype "input"))
    )
    (net (code "48") (name "SDA") (class "Default")
      (node (ref "J3") (pin "3") (pinfunction "3_3") (pintype "passive"))
      (node (ref "R1_PINH") (pin "2") (pinfunction "2_2") (pintype "passive"))
      (node (ref "SENSOR2") (pin "3") (pinfunction "SDI_3") (pintype "bidirectional"))
      (node (ref "U2") (pin "19") (pinfunction "IO21_19") (pintype "bidirectional"))
      (node (ref "U3") (pin "15") (pinfunction "SDA_15") (pintype "bidirectional"))
      (node (ref "U4") (pin "8") (pinfunction "SDA_8") (pintype "bidirectional"))
    )
    (net (code "49") (name "SRC") (class "Default")
      (node (ref "C4") (pin "2") (pinfunction "2_2") (pintype "passive"))
      (node (ref "D5") (pin "2") (pinfunction "A_2") (pintype "bidirectional"))
      (node (ref "L1") (pin "1") (pinfunction "1_1") (pintype "passive"))
      (node (ref "Q3") (pin "3") (pinfunction "D_3") (pintype "bidirectional"))
    )
    (net (code "50") (name "SS_SD") (class "Default")
      (node (ref "D8") (pin "2") (pinfunction "2_2") (pintype "passive"))
      (node (ref "J4") (pin "P2") (pinfunction "CD/DAT3_P2") (pintype "bidirectional"))
      (node (ref "R10") (pin "2") (pinfunction "2_2") (pintype "passive"))
      (node (ref "U2") (pin "4") (pinfunction "IO4_4") (pintype "bidirectional"))
    )
    (net (code "51") (name "TX") (class "Default")
      (node (ref "TP1") (pin "TP") (pinfunction "TP_TP") (pintype "input"))
      (node (ref "U2") (pin "25") (pinfunction "TXD0/GPIO16_25") (pintype "bidirectional"))
    )
    (net (code "52") (name "USB_D+") (class "Default")
      (node (ref "D1") (pin "1") (pinfunction "I/O1_1_1") (pintype "bidirectional"))
      (node (ref "U2") (pin "14") (pinfunction "IO13_14") (pintype "bidirectional"))
    )
    (net (code "53") (name "USB_D-") (class "Default")
      (node (ref "D1") (pin "3") (pinfunction "I/O2_1_3") (pintype "bidirectional"))
      (node (ref "U2") (pin "13") (pinfunction "IO12_13") (pintype "bidirectional"))
    )
    (net (code "54") (name "VBAT") (class "Default")
      (node (ref "C2_BAT") (pin "1") (pinfunction "1_1") (pintype "passive"))
      (node (ref "MCP73831") (pin "3") (pinfunction "VBAT_3") (pintype "power_in"))
      (node (ref "Q1") (pin "3") (pinfunction "D_3") (pintype "bidirectional"))
      (node (ref "TP3") (pin "TP") (pinfunction "TP_TP") (pintype "input"))
      (node (ref "U4") (pin "2") (pinfunction "CELL_2") (pintype "power_in"))
      (node (ref "U4") (pin "3") (pinfunction "VDD_3") (pintype "power_in"))
    )
    (net (code "55") (name "VBUS") (class "Default")
      (node (ref "C1_BAT") (pin "1") (pinfunction "1_1") (pintype "passive"))
      (node (ref "C4_USB") (pin "1") (pinfunction "1_1") (pintype "passive"))
      (node (ref "C5_USB") (pin "1") (pinfunction "1_1") (pintype "passive"))
      (node (ref "CHG_LED") (pin "A") (pinfunction "A_A") (pintype "passive"))
      (node (ref "D1") (pin "5") (pinfunction "VBUS_5") (pintype "bidirectional"))
      (node (ref "D2") (pin "2") (pinfunction "ANODE_2") (pintype "bidirectional"))
      (node (ref "MCP73831") (pin "4") (pinfunction "VIN_4") (pintype "power_in"))
      (node (ref "PFMF.050.1") (pin "2") (pinfunction "2_2") (pintype "passive"))
      (node (ref "Q1") (pin "1") (pinfunction "G_1") (pintype "bidirectional"))
      (node (ref "R1_PWRUSB") (pin "2") (pinfunction "2_2") (pintype "passive"))
      (node (ref "TP14") (pin "TP") (pinfunction "TP_TP") (pintype "input"))
    )
    (net (code "56") (name "VRTC") (class "Default")
      (node (ref "C10_SUPERCAP") (pin "2") (pinfunction "2_2") (pintype "passive"))
      (node (ref "C8") (pin "2") (pinfunction "2_2") (pintype "passive"))
      (node (ref "R_CAPACITOR") (pin "2") (pinfunction "2_2") (pintype "passive"))
      (node (ref "U3") (pin "14") (pinfunction "VBAT_14") (pintype "power_in"))
    )
    (net (code "57") (name "VUSB") (class "Default")
      (node (ref "J2") (pin "A4") (pinfunction "A4_A4") (pintype "bidirectional"))
      (node (ref "J2") (pin "A9") (pinfunction "A9_A9") (pintype "bidirectional"))
      (node (ref "J2") (pin "B4") (pinfunction "B4_B4") (pintype "bidirectional"))
      (node (ref "J2") (pin "B9") (pinfunction "B9_B9") (pintype "bidirectional"))
      (node (ref "PFMF.050.1") (pin "1") (pinfunction "1_1") (pintype "passive"))
    )
    (net (code "58") (name "unconnected-(IC1-NC-Pad4)") (class "Default")
      (node (ref "IC1") (pin "4") (pinfunction "NC_4") (pintype "no_connect"))
    )
    (net (code "59") (name "unconnected-(IC1-VDD-Pad2)") (class "Default")
      (node (ref "IC1") (pin "2") (pinfunction "VDD_2") (pintype "bidirectional"))
    )
    (net (code "60") (name "unconnected-(IC4-NC-Pad4)") (class "Default")
      (node (ref "IC4") (pin "4") (pinfunction "NC_4") (pintype "no_connect"))
    )
    (net (code "61") (name "unconnected-(J1-Pad1)") (class "Default")
      (node (ref "J1") (pin "1") (pinfunction "1_1") (pintype "bidirectional"))
    )
    (net (code "62") (name "unconnected-(J1-Pad6)") (class "Default")
      (node (ref "J1") (pin "6") (pinfunction "6_6") (pintype "bidirectional"))
    )
    (net (code "63") (name "unconnected-(J1-Pad7)") (class "Default")
      (node (ref "J1") (pin "7") (pinfunction "7_7") (pintype "bidirectional"))
    )
    (net (code "64") (name "unconnected-(J2-PadA8)") (class "Default")
      (node (ref "J2") (pin "A8") (pinfunction "A8_A8") (pintype "bidirectional"))
    )
    (net (code "65") (name "unconnected-(J2-PadB8)") (class "Default")
      (node (ref "J2") (pin "B8") (pinfunction "B8_B8") (pintype "bidirectional"))
    )
    (net (code "66") (name "unconnected-(J4-DAT1-PadP8)") (class "Default")
      (node (ref "J4") (pin "P8") (pinfunction "DAT1_P8") (pintype "bidirectional"))
    )
    (net (code "67") (name "unconnected-(J4-DAT2-PadP1)") (class "Default")
      (node (ref "J4") (pin "P1") (pinfunction "DAT2_P1") (pintype "bidirectional"))
    )
    (net (code "68") (name "unconnected-(J4-DETECTION_1-PadS1)") (class "Default")
      (node (ref "J4") (pin "S1") (pinfunction "DETECTION_1_S1") (pintype "bidirectional"))
    )
    (net (code "69") (name "unconnected-(J4-DETECTION_2-PadS2)") (class "Default")
      (node (ref "J4") (pin "S2") (pinfunction "DETECTION_2_S2") (pintype "bidirectional"))
    )
    (net (code "70") (name "unconnected-(U2-NC-Pad22)") (class "Default")
      (node (ref "U2") (pin "22") (pinfunction "NC_22") (pintype "no_connect"))
    )
    (net (code "71") (name "unconnected-(U4-~{ALERT}-Pad5)") (class "Default")
      (node (ref "U4") (pin "5") (pinfunction "~{ALERT}_5") (pintype "output"))
    )
  )
)
